# Loadcell_board.net
KiCad netlist of a schematic drawn in EAGLE
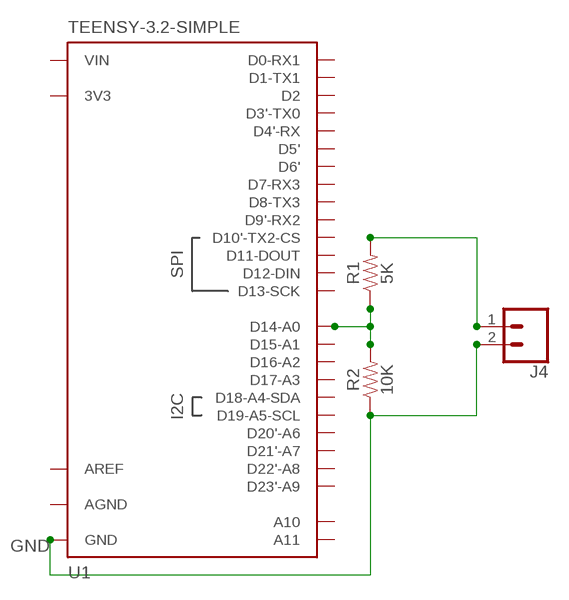
[diagram p0: schematic, sheet 1]

(export (version "E")
  (design (tool "Eeschema 10.0.6"))
  (components
    (comp (ref "J4")
      (value "CONN_02")
      (footprint "eagle-import:1X02")
      (libsource (lib "eagle-import") (part "CONN_02"))
    )
    (comp (ref "R1")
      (value "5K")
      (footprint "eagle-import:AXIAL-0.3")
      (libsource (lib "eagle-import") (part "1KOHM-HORIZ-1/4W-5%"))
    )
    (comp (ref "R2")
      (value "10K")
      (footprint "eagle-import:AXIAL-0.3")
      (libsource (lib "eagle-import") (part "1KOHM-HORIZ-1/4W-5%"))
    )
    (comp (ref "U1")
      (value "TEENSY-3.2-SIMPLE")
      (footprint "eagle-import:TEENSY-3.2-SIMPLE")
      (libsource (lib "eagle-import") (part "TEENSY-3.2-SIMPLE"))
    )
  )
  (nets
    (net (code "1") (name "/3V3") (class "Default")
      (node (ref "U1") (pin "3.3V") (pinfunction "3V3_3.3V") (pintype "power_in"))
    )
    (net (code "2") (name "/AGND") (class "Default")
      (node (ref "U1") (pin "AGND") (pinfunction "AGND_AGND") (pintype "power_in"))
    )
    (net (code "3") (name "/AREF") (class "Default")
      (node (ref "U1") (pin "AREF") (pinfunction "AREF_AREF") (pintype "power_in"))
    )
    (net (code "4") (name "/GND") (class "Default")
      (node (ref "J4") (pin "2") (pinfunction "2_2") (pintype "passive"))
      (node (ref "R2") (pin "P$1") (pinfunction "1_P$1") (pintype "passive"))
      (node (ref "U1") (pin "GND") (pinfunction "GND_GND") (pintype "power_in"))
    )
    (net (code "5") (name "/VIN") (class "Default")
      (node (ref "U1") (pin "VIN") (pinfunction "VIN_VIN") (pintype "power_in"))
    )
    (net (code "6") (name "Net-(R1-1)") (class "Default")
      (node (ref "R1") (pin "P$1") (pinfunction "1_P$1") (pintype "passive"))
      (node (ref "R2") (pin "P$2") (pinfunction "2_P$2") (pintype "passive"))
      (node (ref "U1") (pin "14") (pinfunction "D14-A0_14") (pintype "bidirectional"))
    )
    (net (code "7") (name "Net-(R1-2)") (class "Default")
      (node (ref "J4") (pin "1") (pinfunction "1_1") (pintype "passive"))
      (node (ref "R1") (pin "P$2") (pinfunction "2_P$2") (pintype "passive"))
    )
    (net (code "8") (name "unconnected-(U1-D0-RX1-Pad0)") (class "Default")
      (node (ref "U1") (pin "0") (pinfunction "D0-RX1_0") (pintype "bidirectional"))
    )
    (net (code "9") (name "unconnected-(U1-D1-TX1-Pad1)") (class "Default")
      (node (ref "U1") (pin "1") (pinfunction "D1-TX1_1") (pintype "bidirectional"))
    )
    (net (code "10") (name "unconnected-(U1-D2-Pad2)") (class "Default")
      (node (ref "U1") (pin "2") (pinfunction "D2_2") (pintype "bidirectional"))
    )
    (net (code "11") (name "unconnected-(U1-D3'-TX0-Pad3)") (class "Default")
      (node (ref "U1") (pin "3") (pinfunction "D3'-TX0_3") (pintype "bidirectional"))
    )
    (net (code "12") (name "unconnected-(U1-D4'-RX-Pad4)") (class "Default")
      (node (ref "U1") (pin "4") (pinfunction "D4'-RX_4") (pintype "bidirectional"))
    )
    (net (code "13") (name "unconnected-(U1-D5'-Pad5)") (class "Default")
      (node (ref "U1") (pin "5") (pinfunction "D5'_5") (pintype "bidirectional"))
    )
    (net (code "14") (name "unconnected-(U1-D6'-Pad6)") (class "Default")
      (node (ref "U1") (pin "6") (pinfunction "D6'_6") (pintype "bidirectional"))
    )
    (net (code "15") (name "unconnected-(U1-D7-RX3-Pad7)") (class "Default")
      (node (ref "U1") (pin "7") (pinfunction "D7-RX3_7") (pintype "bidirectional"))
    )
    (net (code "16") (name "unconnected-(U1-D8-TX3-Pad8)") (class "Default")
      (node (ref "U1") (pin "8") (pinfunction "D8-TX3_8") (pintype "bidirectional"))
    )
    (net (code "17") (name "unconnected-(U1-D9'-RX2-Pad9)") (class "Default")
      (node (ref "U1") (pin "9") (pinfunction "D9'-RX2_9") (pintype "bidirectional"))
    )
    (net (code "18") (name "unconnected-(U1-D10'-TX2-CS-Pad10)") (class "Default")
      (node (ref "U1") (pin "10") (pinfunction "D10'-TX2-CS_10") (pintype "bidirectional"))
    )
    (net (code "19") (name "unconnected-(U1-D11-DOUT-Pad11)") (class "Default")
      (node (ref "U1") (pin "11") (pinfunction "D11-DOUT_11") (pintype "bidirectional"))
    )
    (net (code "20") (name "unconnected-(U1-D12-DIN-Pad12)") (class "Default")
      (node (ref "U1") (pin "12") (pinfunction "D12-DIN_12") (pintype "bidirectional"))
    )
    (net (code "21") (name "unconnected-(U1-D13-SCK-Pad13)") (class "Default")
      (node (ref "U1") (pin "13") (pinfunction "D13-SCK_13") (pintype "bidirectional"))
    )
    (net (code "22") (name "unconnected-(U1-D15-A1-Pad15)") (class "Default")
      (node (ref "U1") (pin "15") (pinfunction "D15-A1_15") (pintype "bidirectional"))
    )
    (net (code "23") (name "unconnected-(U1-D16-A2-Pad16)") (class "Default")
      (node (ref "U1") (pin "16") (pinfunction "D16-A2_16") (pintype "bidirectional"))
    )
    (net (code "24") (name "unconnected-(U1-D17-A3-Pad17)") (class "Default")
      (node (ref "U1") (pin "17") (pinfunction "D17-A3_17") (pintype "bidirectional"))
    )
    (net (code "25") (name "unconnected-(U1-D18-A4-SDA-Pad18)") (class "Default")
      (node (ref "U1") (pin "18") (pinfunction "D18-A4-SDA_18") (pintype "bidirectional"))
    )
    (net (code "26") (name "unconnected-(U1-D19-A5-SCL-Pad19)") (class "Default")
      (node (ref "U1") (pin "19") (pinfunction "D19-A5-SCL_19") (pintype "bidirectional"))
    )
    (net (code "27") (name "unconnected-(U1-D20'-A6-Pad20)") (class "Default")
      (node (ref "U1") (pin "20") (pinfunction "D20'-A6_20") (pintype "bidirectional"))
    )
    (net (code "28") (name "unconnected-(U1-D21'-A7-Pad21)") (class "Default")
      (node (ref "U1") (pin "21") (pinfunction "D21'-A7_21") (pintype "bidirectional"))
    )
    (net (code "29") (name "unconnected-(U1-D22'-A8-Pad22)") (class "Default")
      (node (ref "U1") (pin "22") (pinfunction "D22'-A8_22") (pintype "bidirectional"))
    )
    (net (code "30") (name "unconnected-(U1-D23'-A9-Pad23)") (class "Default")
      (node (ref "U1") (pin "23") (pinfunction "D23'-A9_23") (pintype "bidirectional"))
    )
    (net (code "31") (name "unconnected-(U1-PadA10)") (class "Default")
      (node (ref "U1") (pin "A10") (pinfunction "A10_A10") (pintype "bidirectional"))
    )
    (net (code "32") (name "unconnected-(U1-PadA11)") (class "Default")
      (node (ref "U1") (pin "A11") (pinfunction "A11_A11") (pintype "bidirectional"))
    )
  )
)
